# IcosaCharlieCylon.net
KiCad netlist of a schematic drawn in EAGLE
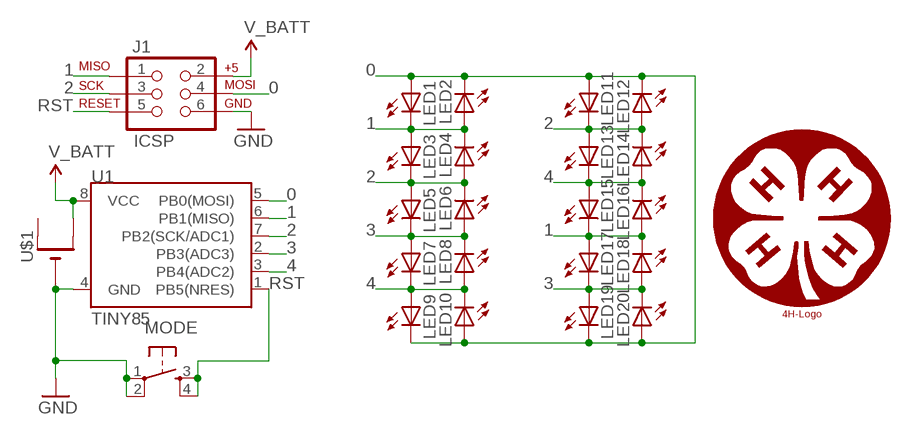
[diagram p0: schematic, sheet 1]

(export (version "E")
  (design (tool "Eeschema 10.0.6"))
  (components
    (comp (ref "J1")
      (value "ICSP")
      (footprint "eagle-import:2X3-NS")
      (libsource (lib "eagle-import") (part "AVR_SPI_PRG_6LABELED"))
    )
    (comp (ref "LED1")
      (value "LEDOVAL")
      (footprint "eagle-import:LED-OVAL")
      (libsource (lib "eagle-import") (part "LEDOVAL"))
    )
    (comp (ref "LED2")
      (value "LEDOVAL")
      (footprint "eagle-import:LED-OVAL")
      (libsource (lib "eagle-import") (part "LEDOVAL"))
    )
    (comp (ref "LED3")
      (value "LEDOVAL")
      (footprint "eagle-import:LED-OVAL")
      (libsource (lib "eagle-import") (part "LEDOVAL"))
    )
    (comp (ref "LED4")
      (value "LEDOVAL")
      (footprint "eagle-import:LED-OVAL")
      (libsource (lib "eagle-import") (part "LEDOVAL"))
    )
    (comp (ref "LED5")
      (value "LEDOVAL")
      (footprint "eagle-import:LED-OVAL")
      (libsource (lib "eagle-import") (part "LEDOVAL"))
    )
    (comp (ref "LED6")
      (value "LEDOVAL")
      (footprint "eagle-import:LED-OVAL")
      (libsource (lib "eagle-import") (part "LEDOVAL"))
    )
    (comp (ref "LED7")
      (value "LEDOVAL")
      (footprint "eagle-import:LED-OVAL")
      (libsource (lib "eagle-import") (part "LEDOVAL"))
    )
    (comp (ref "LED8")
      (value "LEDOVAL")
      (footprint "eagle-import:LED-OVAL")
      (libsource (lib "eagle-import") (part "LEDOVAL"))
    )
    (comp (ref "LED9")
      (value "LEDOVAL")
      (footprint "eagle-import:LED-OVAL")
      (libsource (lib "eagle-import") (part "LEDOVAL"))
    )
    (comp (ref "LED10")
      (value "LEDOVAL")
      (footprint "eagle-import:LED-OVAL")
      (libsource (lib "eagle-import") (part "LEDOVAL"))
    )
    (comp (ref "LED11")
      (value "LEDOVAL")
      (footprint "eagle-import:LED-OVAL")
      (libsource (lib "eagle-import") (part "LEDOVAL"))
    )
    (comp (ref "LED12")
      (value "LEDOVAL")
      (footprint "eagle-import:LED-OVAL")
      (libsource (lib "eagle-import") (part "LEDOVAL"))
    )
    (comp (ref "LED13")
      (value "LEDOVAL")
      (footprint "eagle-import:LED-OVAL")
      (libsource (lib "eagle-import") (part "LEDOVAL"))
    )
    (comp (ref "LED14")
      (value "LEDOVAL")
      (footprint "eagle-import:LED-OVAL")
      (libsource (lib "eagle-import") (part "LEDOVAL"))
    )
    (comp (ref "LED15")
      (value "LEDOVAL")
      (footprint "eagle-import:LED-OVAL")
      (libsource (lib "eagle-import") (part "LEDOVAL"))
    )
    (comp (ref "LED16")
      (value "LEDOVAL")
      (footprint "eagle-import:LED-OVAL")
      (libsource (lib "eagle-import") (part "LEDOVAL"))
    )
    (comp (ref "LED17")
      (value "LEDOVAL")
      (footprint "eagle-import:LED-OVAL")
      (libsource (lib "eagle-import") (part "LEDOVAL"))
    )
    (comp (ref "LED18")
      (value "LEDOVAL")
      (footprint "eagle-import:LED-OVAL")
      (libsource (lib "eagle-import") (part "LEDOVAL"))
    )
    (comp (ref "LED19")
      (value "LEDOVAL")
      (footprint "eagle-import:LED-OVAL")
      (libsource (lib "eagle-import") (part "LEDOVAL"))
    )
    (comp (ref "LED20")
      (value "LEDOVAL")
      (footprint "eagle-import:LED-OVAL")
      (libsource (lib "eagle-import") (part "LEDOVAL"))
    )
    (comp (ref "MODE")
      (value "TAC_SWITCHPTH")
      (footprint "eagle-import:TACTILE-PTH")
      (libsource (lib "eagle-import") (part "TAC_SWITCHPTH"))
    )
    (comp (ref "U$1")
      (value "CR2032THM")
      (footprint "eagle-import:CR2032-THRU")
      (libsource (lib "eagle-import") (part "CR2032THM"))
    )
    (comp (ref "U$3")
      (value "4H-LOGO6")
      (footprint "eagle-import:4H_LOGO_6")
      (libsource (lib "eagle-import") (part "4H-LOGO6"))
    )
    (comp (ref "U1")
      (value "TINY85")
      (footprint "eagle-import:DIP08")
      (libsource (lib "eagle-import") (part "ATTINY45TINY85-20-DIP"))
    )
  )
  (nets
    (net (code "1") (name "/0") (class "Default")
      (node (ref "J1") (pin "4") (pinfunction "MOSI_4") (pintype "passive"))
      (node (ref "LED1") (pin "ANODE") (pinfunction "A_ANODE") (pintype "passive"))
      (node (ref "LED10") (pin "ANODE") (pinfunction "A_ANODE") (pintype "passive"))
      (node (ref "LED11") (pin "ANODE") (pinfunction "A_ANODE") (pintype "passive"))
      (node (ref "LED12") (pin "CATHODE") (pinfunction "C_CATHODE") (pintype "passive"))
      (node (ref "LED19") (pin "CATHODE") (pinfunction "C_CATHODE") (pintype "passive"))
      (node (ref "LED2") (pin "CATHODE") (pinfunction "C_CATHODE") (pintype "passive"))
      (node (ref "LED20") (pin "ANODE") (pinfunction "A_ANODE") (pintype "passive"))
      (node (ref "LED9") (pin "CATHODE") (pinfunction "C_CATHODE") (pintype "passive"))
      (node (ref "U1") (pin "5") (pinfunction "PB0(MOSI)_5") (pintype "bidirectional"))
    )
    (net (code "2") (name "/1") (class "Default")
      (node (ref "J1") (pin "1") (pinfunction "MISO_1") (pintype "passive"))
      (node (ref "LED1") (pin "CATHODE") (pinfunction "C_CATHODE") (pintype "passive"))
      (node (ref "LED15") (pin "CATHODE") (pinfunction "C_CATHODE") (pintype "passive"))
      (node (ref "LED16") (pin "ANODE") (pinfunction "A_ANODE") (pintype "passive"))
      (node (ref "LED17") (pin "ANODE") (pinfunction "A_ANODE") (pintype "passive"))
      (node (ref "LED18") (pin "CATHODE") (pinfunction "C_CATHODE") (pintype "passive"))
      (node (ref "LED2") (pin "ANODE") (pinfunction "A_ANODE") (pintype "passive"))
      (node (ref "LED3") (pin "ANODE") (pinfunction "A_ANODE") (pintype "passive"))
      (node (ref "LED4") (pin "CATHODE") (pinfunction "C_CATHODE") (pintype "passive"))
      (node (ref "U1") (pin "6") (pinfunction "PB1(MISO)_6") (pintype "bidirectional"))
    )
    (net (code "3") (name "/2") (class "Default")
      (node (ref "J1") (pin "3") (pinfunction "SCK_3") (pintype "passive"))
      (node (ref "LED11") (pin "CATHODE") (pinfunction "C_CATHODE") (pintype "passive"))
      (node (ref "LED12") (pin "ANODE") (pinfunction "A_ANODE") (pintype "passive"))
      (node (ref "LED13") (pin "ANODE") (pinfunction "A_ANODE") (pintype "passive"))
      (node (ref "LED14") (pin "CATHODE") (pinfunction "C_CATHODE") (pintype "passive"))
      (node (ref "LED3") (pin "CATHODE") (pinfunction "C_CATHODE") (pintype "passive"))
      (node (ref "LED4") (pin "ANODE") (pinfunction "A_ANODE") (pintype "passive"))
      (node (ref "LED5") (pin "ANODE") (pinfunction "A_ANODE") (pintype "passive"))
      (node (ref "LED6") (pin "CATHODE") (pinfunction "C_CATHODE") (pintype "passive"))
      (node (ref "U1") (pin "7") (pinfunction "PB2(SCK/ADC1)_7") (pintype "bidirectional"))
    )
    (net (code "4") (name "/3") (class "Default")
      (node (ref "LED17") (pin "CATHODE") (pinfunction "C_CATHODE") (pintype "passive"))
      (node (ref "LED18") (pin "ANODE") (pinfunction "A_ANODE") (pintype "passive"))
      (node (ref "LED19") (pin "ANODE") (pinfunction "A_ANODE") (pintype "passive"))
      (node (ref "LED20") (pin "CATHODE") (pinfunction "C_CATHODE") (pintype "passive"))
      (node (ref "LED5") (pin "CATHODE") (pinfunction "C_CATHODE") (pintype "passive"))
      (node (ref "LED6") (pin "ANODE") (pinfunction "A_ANODE") (pintype "passive"))
      (node (ref "LED7") (pin "ANODE") (pinfunction "A_ANODE") (pintype "passive"))
      (node (ref "LED8") (pin "CATHODE") (pinfunction "C_CATHODE") (pintype "passive"))
      (node (ref "U1") (pin "2") (pinfunction "PB3(ADC3)_2") (pintype "bidirectional"))
    )
    (net (code "5") (name "/4") (class "Default")
      (node (ref "LED10") (pin "CATHODE") (pinfunction "C_CATHODE") (pintype "passive"))
      (node (ref "LED13") (pin "CATHODE") (pinfunction "C_CATHODE") (pintype "passive"))
      (node (ref "LED14") (pin "ANODE") (pinfunction "A_ANODE") (pintype "passive"))
      (node (ref "LED15") (pin "ANODE") (pinfunction "A_ANODE") (pintype "passive"))
      (node (ref "LED16") (pin "CATHODE") (pinfunction "C_CATHODE") (pintype "passive"))
      (node (ref "LED7") (pin "CATHODE") (pinfunction "C_CATHODE") (pintype "passive"))
      (node (ref "LED8") (pin "ANODE") (pinfunction "A_ANODE") (pintype "passive"))
      (node (ref "LED9") (pin "ANODE") (pinfunction "A_ANODE") (pintype "passive"))
      (node (ref "U1") (pin "3") (pinfunction "PB4(ADC2)_3") (pintype "bidirectional"))
    )
    (net (code "6") (name "/RST") (class "Default")
      (node (ref "J1") (pin "5") (pinfunction "RST_5") (pintype "passive"))
      (node (ref "MODE") (pin "3") (pinfunction "3_3") (pintype "passive"))
      (node (ref "MODE") (pin "4") (pinfunction "4_4") (pintype "passive"))
      (node (ref "U1") (pin "1") (pinfunction "PB5(NRES)_1") (pintype "bidirectional"))
    )
    (net (code "7") (name "GND") (class "Default")
      (node (ref "J1") (pin "6") (pinfunction "GND_6") (pintype "passive"))
      (node (ref "MODE") (pin "1") (pinfunction "1_1") (pintype "passive"))
      (node (ref "MODE") (pin "2") (pinfunction "2_2") (pintype "passive"))
      (node (ref "U$1") (pin "-") (pinfunction "-_-") (pintype "passive"))
      (node (ref "U1") (pin "4") (pinfunction "GND_4") (pintype "bidirectional"))
    )
    (net (code "8") (name "V_BATT") (class "Default")
      (node (ref "J1") (pin "2") (pinfunction "V+_2") (pintype "passive"))
      (node (ref "U$1") (pin "+2") (pinfunction "+1_+2") (pintype "passive"))
      (node (ref "U1") (pin "8") (pinfunction "VCC_8") (pintype "bidirectional"))
    )
    (net (code "9") (name "unconnected-(U$1-+-Pad+1)") (class "Default")
      (node (ref "U$1") (pin "+1") (pinfunction "+_+1") (pintype "passive"))
    )
  )
)
